# source_eagle.net
KiCad netlist of a schematic drawn in EAGLE
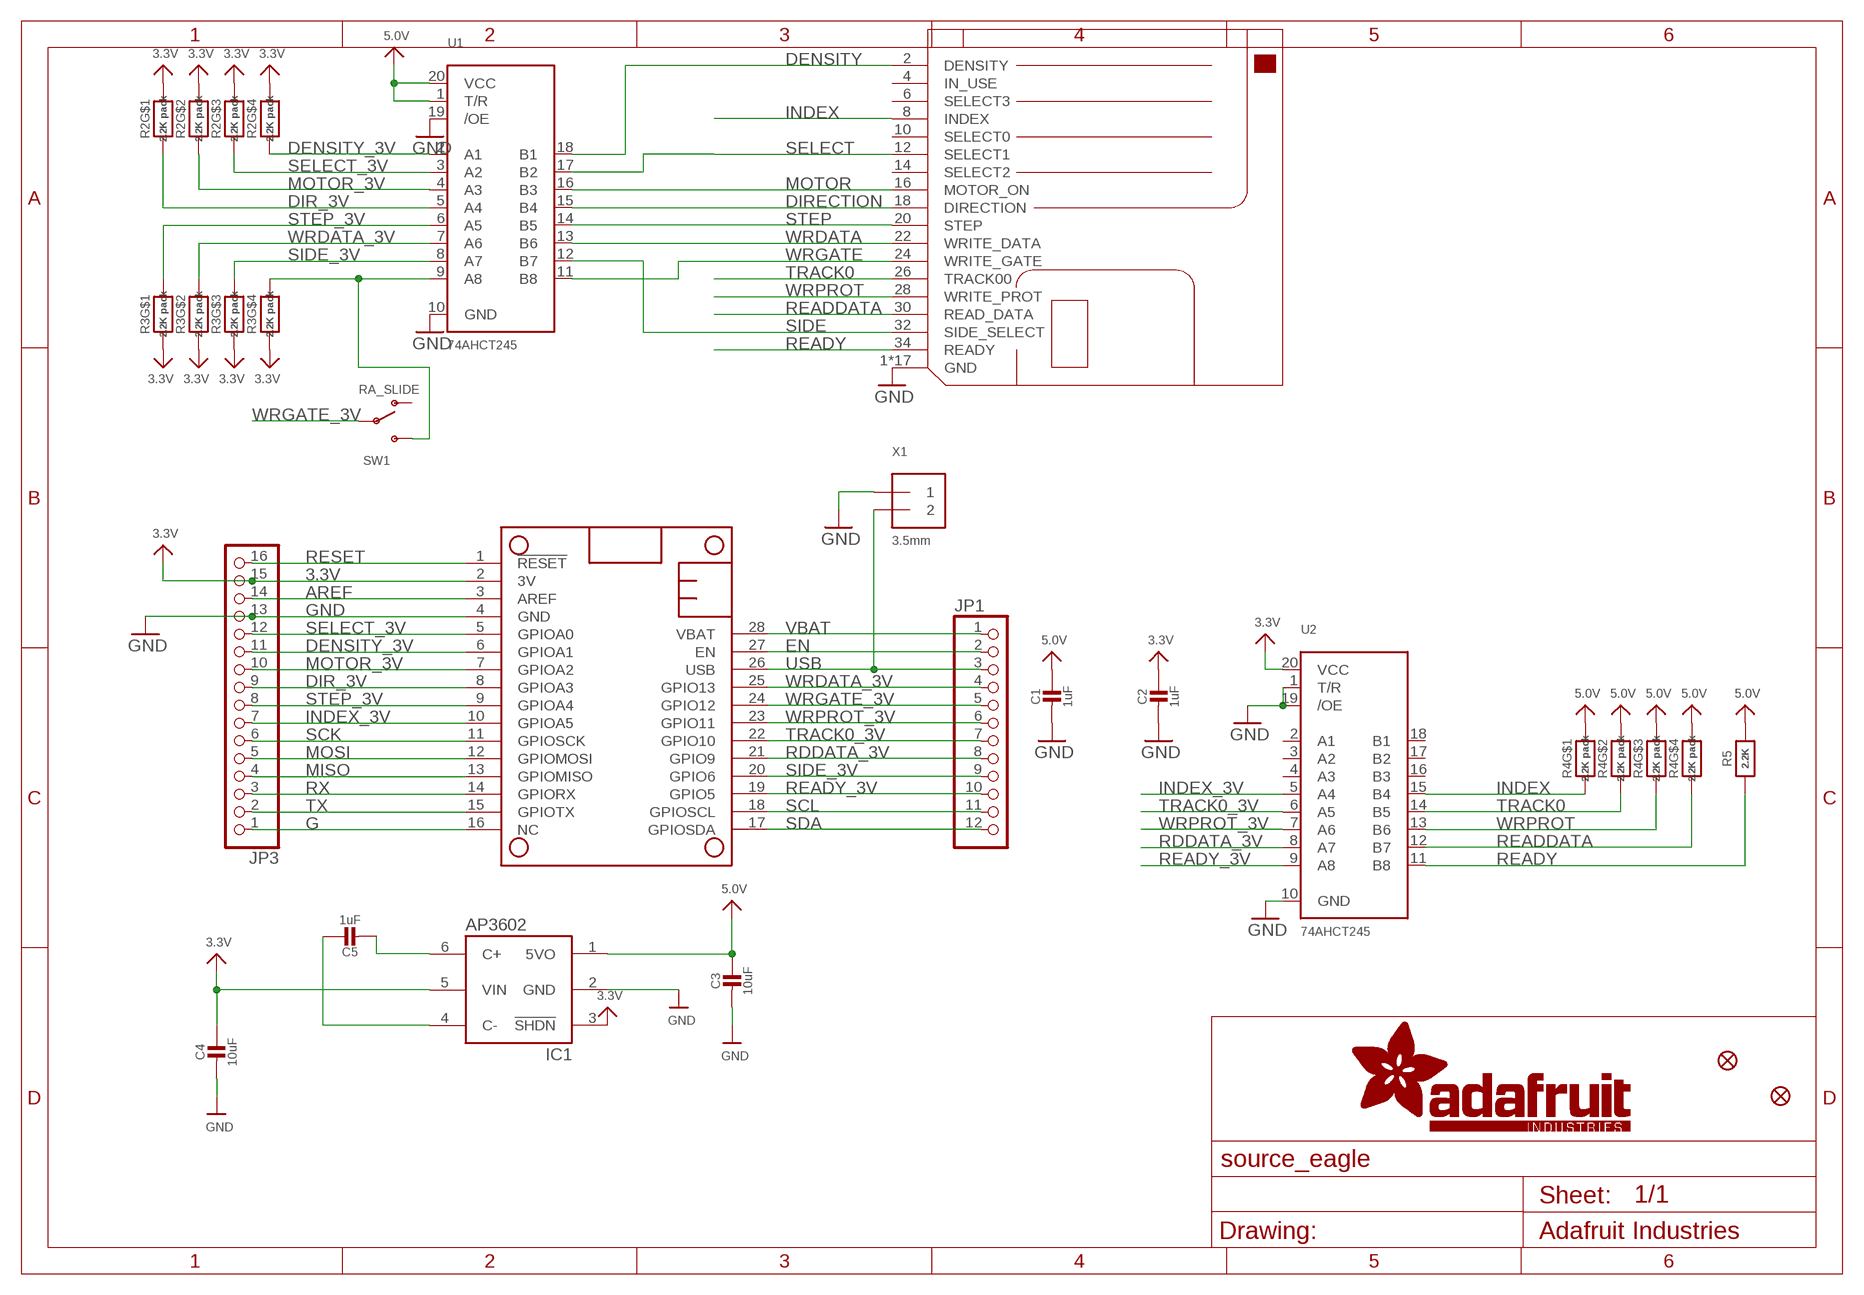
[diagram p0: schematic, sheet 1]

(export (version "E")
  (design (tool "Eeschema 10.0.6"))
  (components
    (comp (ref "C1")
      (value "1uF")
      (footprint "eagle-import:0603-NO")
      (libsource (lib "eagle-import") (part "CAP_CERAMIC0603_NO"))
    )
    (comp (ref "C2")
      (value "1uF")
      (footprint "eagle-import:0603-NO")
      (libsource (lib "eagle-import") (part "CAP_CERAMIC0603_NO"))
    )
    (comp (ref "C3")
      (value "10uF")
      (footprint "eagle-import:0805-NO")
      (libsource (lib "eagle-import") (part "CAP_CERAMIC0805-NOOUTLINE"))
    )
    (comp (ref "C4")
      (value "10uF")
      (footprint "eagle-import:0805-NO")
      (libsource (lib "eagle-import") (part "CAP_CERAMIC0805-NOOUTLINE"))
    )
    (comp (ref "C5")
      (value "1uF")
      (footprint "eagle-import:0603-NO")
      (libsource (lib "eagle-import") (part "CAP_CERAMIC0603_NO"))
    )
    (comp (ref "FDD1")
      (value "FLOPPY_IDC_SMT")
      (footprint "eagle-import:2X17_FLOPPY_SMTIDC")
      (libsource (lib "eagle-import") (part "FLOPPY_IDC_SMT"))
    )
    (comp (ref "FID1")
      (value "FIDUCIAL_1MM")
      (footprint "eagle-import:FIDUCIAL_1MM")
      (libsource (lib "eagle-import") (part "FIDUCIAL_1MM"))
    )
    (comp (ref "FID2")
      (value "FIDUCIAL_1MM")
      (footprint "eagle-import:FIDUCIAL_1MM")
      (libsource (lib "eagle-import") (part "FIDUCIAL_1MM"))
    )
    (comp (ref "IC1")
      (value "AP3602")
      (footprint "eagle-import:SOT23-6")
      (libsource (lib "eagle-import") (part "AP3602"))
    )
    (comp (ref "JP1")
      (value "HEADER-1X12")
      (footprint "eagle-import:1X12_ROUND")
      (libsource (lib "eagle-import") (part "HEADER-1X12"))
    )
    (comp (ref "JP3")
      (value "HEADER-1X16ROUND")
      (footprint "eagle-import:1X16_ROUND")
      (libsource (lib "eagle-import") (part "HEADER-1X16ROUND"))
    )
    (comp (ref "MS1")
      (value "FEATHERWING")
      (footprint "eagle-import:FEATHERWING")
      (libsource (lib "eagle-import") (part "FEATHERWING"))
    )
    (comp (ref "R2")
      (value "2.2K pack")
      (footprint "eagle-import:RESPACK_4X0603")
      (libsource (lib "eagle-import") (part "RESISTOR_4PACK"))
    )
    (comp (ref "R3")
      (value "2.2K pack")
      (footprint "eagle-import:RESPACK_4X0603")
      (libsource (lib "eagle-import") (part "RESISTOR_4PACK"))
    )
    (comp (ref "R4")
      (value "2.2K pack")
      (footprint "eagle-import:RESPACK_4X0603")
      (libsource (lib "eagle-import") (part "RESISTOR_4PACK"))
    )
    (comp (ref "R5")
      (value "2.2K")
      (footprint "eagle-import:0603-NO")
      (libsource (lib "eagle-import") (part "RESISTOR_0603_NOOUT"))
    )
    (comp (ref "SW1")
      (value "RA_SLIDE")
      (footprint "eagle-import:SPDT_SMT_SSSS811101")
      (libsource (lib "eagle-import") (part "SWITCH_SPDT"))
    )
    (comp (ref "U1")
      (value "74AHCT245")
      (footprint "eagle-import:SSOP20")
      (libsource (lib "eagle-import") (part "74LCX245_SSOP20"))
    )
    (comp (ref "U2")
      (value "74AHCT245")
      (footprint "eagle-import:SSOP20")
      (libsource (lib "eagle-import") (part "74LCX245_SSOP20"))
    )
    (comp (ref "X1")
      (value "3.5mm")
      (footprint "eagle-import:TERMBLOCK_1X2-3.5MM")
      (libsource (lib "eagle-import") (part "TERMBLOCK_1X2_3.5MM"))
    )
  )
  (nets
    (net (code "1") (name "/AREF") (class "Default")
      (node (ref "JP3") (pin "14") (pinfunction "14_14") (pintype "passive"))
      (node (ref "MS1") (pin "3") (pinfunction "AREF_3") (pintype "passive"))
    )
    (net (code "2") (name "/DENSITY") (class "Default")
      (node (ref "FDD1") (pin "2") (pinfunction "DENSITY_2") (pintype "input"))
      (node (ref "U1") (pin "18") (pinfunction "B1_18") (pintype "bidirectional"))
    )
    (net (code "3") (name "/DENSITY_3V") (class "Default")
      (node (ref "JP3") (pin "11") (pinfunction "11_11") (pintype "passive"))
      (node (ref "MS1") (pin "6") (pinfunction "GPIOA1_6") (pintype "bidirectional"))
      (node (ref "R2") (pin "4") (pinfunction "1_4") (pintype "passive"))
      (node (ref "U1") (pin "2") (pinfunction "A1_2") (pintype "bidirectional"))
    )
    (net (code "4") (name "/DIRECTION") (class "Default")
      (node (ref "FDD1") (pin "18") (pinfunction "DIRECTION_18") (pintype "input"))
      (node (ref "U1") (pin "15") (pinfunction "B4_15") (pintype "bidirectional"))
    )
    (net (code "5") (name "/DIR_3V") (class "Default")
      (node (ref "JP3") (pin "9") (pinfunction "9_9") (pintype "passive"))
      (node (ref "MS1") (pin "8") (pinfunction "GPIOA3_8") (pintype "bidirectional"))
      (node (ref "R2") (pin "1") (pinfunction "1_1") (pintype "passive"))
      (node (ref "U1") (pin "5") (pinfunction "A4_5") (pintype "bidirectional"))
    )
    (net (code "6") (name "/EN") (class "Default")
      (node (ref "JP1") (pin "2") (pinfunction "2_2") (pintype "passive"))
      (node (ref "MS1") (pin "27") (pinfunction "EN_27") (pintype "passive"))
    )
    (net (code "7") (name "/G") (class "Default")
      (node (ref "JP3") (pin "1") (pinfunction "1_1") (pintype "passive"))
      (node (ref "MS1") (pin "16") (pinfunction "NC_16") (pintype "passive"))
    )
    (net (code "8") (name "/INDEX") (class "Default")
      (node (ref "FDD1") (pin "8") (pinfunction "INDEX_8") (pintype "output"))
      (node (ref "R4") (pin "1") (pinfunction "1_1") (pintype "passive"))
      (node (ref "U2") (pin "15") (pinfunction "B4_15") (pintype "bidirectional"))
    )
    (net (code "9") (name "/INDEX_3V") (class "Default")
      (node (ref "JP3") (pin "7") (pinfunction "7_7") (pintype "passive"))
      (node (ref "MS1") (pin "10") (pinfunction "GPIOA5_10") (pintype "bidirectional"))
      (node (ref "U2") (pin "5") (pinfunction "A4_5") (pintype "bidirectional"))
    )
    (net (code "10") (name "/MISO") (class "Default")
      (node (ref "JP3") (pin "4") (pinfunction "4_4") (pintype "passive"))
      (node (ref "MS1") (pin "13") (pinfunction "GPIOMISO_13") (pintype "bidirectional"))
    )
    (net (code "11") (name "/MOSI") (class "Default")
      (node (ref "JP3") (pin "5") (pinfunction "5_5") (pintype "passive"))
      (node (ref "MS1") (pin "12") (pinfunction "GPIOMOSI_12") (pintype "bidirectional"))
    )
    (net (code "12") (name "/MOTOR") (class "Default")
      (node (ref "FDD1") (pin "16") (pinfunction "MOTOR_ON_16") (pintype "input"))
      (node (ref "U1") (pin "16") (pinfunction "B3_16") (pintype "bidirectional"))
    )
    (net (code "13") (name "/MOTOR_3V") (class "Default")
      (node (ref "JP3") (pin "10") (pinfunction "10_10") (pintype "passive"))
      (node (ref "MS1") (pin "7") (pinfunction "GPIOA2_7") (pintype "bidirectional"))
      (node (ref "R2") (pin "2") (pinfunction "1_2") (pintype "passive"))
      (node (ref "U1") (pin "4") (pinfunction "A3_4") (pintype "bidirectional"))
    )
    (net (code "14") (name "/RDDATA_3V") (class "Default")
      (node (ref "JP1") (pin "8") (pinfunction "8_8") (pintype "passive"))
      (node (ref "MS1") (pin "21") (pinfunction "GPIO9_21") (pintype "bidirectional"))
      (node (ref "U2") (pin "8") (pinfunction "A7_8") (pintype "bidirectional"))
    )
    (net (code "15") (name "/READDATA") (class "Default")
      (node (ref "FDD1") (pin "30") (pinfunction "READ_DATA_30") (pintype "output"))
      (node (ref "R4") (pin "4") (pinfunction "1_4") (pintype "passive"))
      (node (ref "U2") (pin "12") (pinfunction "B7_12") (pintype "bidirectional"))
    )
    (net (code "16") (name "/READY") (class "Default")
      (node (ref "FDD1") (pin "34") (pinfunction "READY_34") (pintype "output"))
      (node (ref "R5") (pin "1") (pinfunction "1_1") (pintype "passive"))
      (node (ref "U2") (pin "11") (pinfunction "B8_11") (pintype "bidirectional"))
    )
    (net (code "17") (name "/READY_3V") (class "Default")
      (node (ref "JP1") (pin "10") (pinfunction "10_10") (pintype "passive"))
      (node (ref "MS1") (pin "19") (pinfunction "GPIO5_19") (pintype "bidirectional"))
      (node (ref "U2") (pin "9") (pinfunction "A8_9") (pintype "bidirectional"))
    )
    (net (code "18") (name "/RESET") (class "Default")
      (node (ref "JP3") (pin "16") (pinfunction "16_16") (pintype "passive"))
      (node (ref "MS1") (pin "1") (pinfunction "~{RESET}_1") (pintype "input"))
    )
    (net (code "19") (name "/RX") (class "Default")
      (node (ref "JP3") (pin "3") (pinfunction "3_3") (pintype "passive"))
      (node (ref "MS1") (pin "14") (pinfunction "GPIORX_14") (pintype "bidirectional"))
    )
    (net (code "20") (name "/SCK") (class "Default")
      (node (ref "JP3") (pin "6") (pinfunction "6_6") (pintype "passive"))
      (node (ref "MS1") (pin "11") (pinfunction "GPIOSCK_11") (pintype "bidirectional"))
    )
    (net (code "21") (name "/SCL") (class "Default")
      (node (ref "JP1") (pin "11") (pinfunction "11_11") (pintype "passive"))
      (node (ref "MS1") (pin "18") (pinfunction "GPIOSCL_18") (pintype "bidirectional"))
    )
    (net (code "22") (name "/SDA") (class "Default")
      (node (ref "JP1") (pin "12") (pinfunction "12_12") (pintype "passive"))
      (node (ref "MS1") (pin "17") (pinfunction "GPIOSDA_17") (pintype "bidirectional"))
    )
    (net (code "23") (name "/SELECT") (class "Default")
      (node (ref "FDD1") (pin "12") (pinfunction "SELECT1_12") (pintype "input"))
      (node (ref "U1") (pin "17") (pinfunction "B2_17") (pintype "bidirectional"))
    )
    (net (code "24") (name "/SELECT_3V") (class "Default")
      (node (ref "JP3") (pin "12") (pinfunction "12_12") (pintype "passive"))
      (node (ref "MS1") (pin "5") (pinfunction "GPIOA0_5") (pintype "bidirectional"))
      (node (ref "R2") (pin "3") (pinfunction "1_3") (pintype "passive"))
      (node (ref "U1") (pin "3") (pinfunction "A2_3") (pintype "bidirectional"))
    )
    (net (code "25") (name "/SIDE") (class "Default")
      (node (ref "FDD1") (pin "32") (pinfunction "SIDE_SELECT_32") (pintype "input"))
      (node (ref "U1") (pin "12") (pinfunction "B7_12") (pintype "bidirectional"))
    )
    (net (code "26") (name "/SIDE_3V") (class "Default")
      (node (ref "JP1") (pin "9") (pinfunction "9_9") (pintype "passive"))
      (node (ref "MS1") (pin "20") (pinfunction "GPIO6_20") (pintype "bidirectional"))
      (node (ref "R3") (pin "6") (pinfunction "2_6") (pintype "passive"))
      (node (ref "U1") (pin "8") (pinfunction "A7_8") (pintype "bidirectional"))
    )
    (net (code "27") (name "/STEP") (class "Default")
      (node (ref "FDD1") (pin "20") (pinfunction "STEP_20") (pintype "input"))
      (node (ref "U1") (pin "14") (pinfunction "B5_14") (pintype "bidirectional"))
    )
    (net (code "28") (name "/STEP_3V") (class "Default")
      (node (ref "JP3") (pin "8") (pinfunction "8_8") (pintype "passive"))
      (node (ref "MS1") (pin "9") (pinfunction "GPIOA4_9") (pintype "bidirectional"))
      (node (ref "R3") (pin "8") (pinfunction "2_8") (pintype "passive"))
      (node (ref "U1") (pin "6") (pinfunction "A5_6") (pintype "bidirectional"))
    )
    (net (code "29") (name "/TRACK0") (class "Default")
      (node (ref "FDD1") (pin "26") (pinfunction "TRACK00_26") (pintype "output"))
      (node (ref "R4") (pin "2") (pinfunction "1_2") (pintype "passive"))
      (node (ref "U2") (pin "14") (pinfunction "B5_14") (pintype "bidirectional"))
    )
    (net (code "30") (name "/TRACK0_3V") (class "Default")
      (node (ref "JP1") (pin "7") (pinfunction "7_7") (pintype "passive"))
      (node (ref "MS1") (pin "22") (pinfunction "GPIO10_22") (pintype "bidirectional"))
      (node (ref "U2") (pin "6") (pinfunction "A5_6") (pintype "bidirectional"))
    )
    (net (code "31") (name "/TX") (class "Default")
      (node (ref "JP3") (pin "2") (pinfunction "2_2") (pintype "passive"))
      (node (ref "MS1") (pin "15") (pinfunction "GPIOTX_15") (pintype "bidirectional"))
    )
    (net (code "32") (name "/USB") (class "Default")
      (node (ref "JP1") (pin "3") (pinfunction "3_3") (pintype "passive"))
      (node (ref "MS1") (pin "26") (pinfunction "USB_26") (pintype "power_in"))
      (node (ref "X1") (pin "2") (pinfunction "2_2") (pintype "passive"))
    )
    (net (code "33") (name "/VBAT") (class "Default")
      (node (ref "JP1") (pin "1") (pinfunction "1_1") (pintype "passive"))
      (node (ref "MS1") (pin "28") (pinfunction "VBAT_28") (pintype "power_in"))
    )
    (net (code "34") (name "/WRDATA") (class "Default")
      (node (ref "FDD1") (pin "22") (pinfunction "WRITE_DATA_22") (pintype "input"))
      (node (ref "U1") (pin "13") (pinfunction "B6_13") (pintype "bidirectional"))
    )
    (net (code "35") (name "/WRDATA_3V") (class "Default")
      (node (ref "JP1") (pin "4") (pinfunction "4_4") (pintype "passive"))
      (node (ref "MS1") (pin "25") (pinfunction "GPIO13_25") (pintype "bidirectional"))
      (node (ref "R3") (pin "7") (pinfunction "2_7") (pintype "passive"))
      (node (ref "U1") (pin "7") (pinfunction "A6_7") (pintype "bidirectional"))
    )
    (net (code "36") (name "/WRGATE") (class "Default")
      (node (ref "FDD1") (pin "24") (pinfunction "WRITE_GATE_24") (pintype "input"))
      (node (ref "U1") (pin "11") (pinfunction "B8_11") (pintype "bidirectional"))
    )
    (net (code "37") (name "/WRGATE_3V") (class "Default")
      (node (ref "JP1") (pin "5") (pinfunction "5_5") (pintype "passive"))
      (node (ref "MS1") (pin "24") (pinfunction "GPIO12_24") (pintype "bidirectional"))
      (node (ref "SW1") (pin "B") (pinfunction "P_B") (pintype "passive"))
    )
    (net (code "38") (name "/WRPROT") (class "Default")
      (node (ref "FDD1") (pin "28") (pinfunction "WRITE_PROT_28") (pintype "output"))
      (node (ref "R4") (pin "3") (pinfunction "1_3") (pintype "passive"))
      (node (ref "U2") (pin "13") (pinfunction "B6_13") (pintype "bidirectional"))
    )
    (net (code "39") (name "/WRPROT_3V") (class "Default")
      (node (ref "JP1") (pin "6") (pinfunction "6_6") (pintype "passive"))
      (node (ref "MS1") (pin "23") (pinfunction "GPIO11_23") (pintype "bidirectional"))
      (node (ref "U2") (pin "7") (pinfunction "A6_7") (pintype "bidirectional"))
    )
    (net (code "40") (name "3.3V") (class "Default")
      (node (ref "C2") (pin "1") (pinfunction "1_1") (pintype "passive"))
      (node (ref "C4") (pin "1") (pinfunction "1_1") (pintype "passive"))
      (node (ref "IC1") (pin "3") (pinfunction "~{SHDN}_3") (pintype "input"))
      (node (ref "IC1") (pin "5") (pinfunction "VIN_5") (pintype "power_in"))
      (node (ref "JP3") (pin "15") (pinfunction "15_15") (pintype "passive"))
      (node (ref "MS1") (pin "2") (pinfunction "3V_2") (pintype "power_in"))
      (node (ref "R2") (pin "5") (pinfunction "2_5") (pintype "passive"))
      (node (ref "R2") (pin "6") (pinfunction "2_6") (pintype "passive"))
      (node (ref "R2") (pin "7") (pinfunction "2_7") (pintype "passive"))
      (node (ref "R2") (pin "8") (pinfunction "2_8") (pintype "passive"))
      (node (ref "R3") (pin "1") (pinfunction "1_1") (pintype "passive"))
      (node (ref "R3") (pin "2") (pinfunction "1_2") (pintype "passive"))
      (node (ref "R3") (pin "3") (pinfunction "1_3") (pintype "passive"))
      (node (ref "R3") (pin "4") (pinfunction "1_4") (pintype "passive"))
      (node (ref "U2") (pin "20") (pinfunction "VCC_20") (pintype "bidirectional"))
    )
    (net (code "41") (name "5.0V") (class "Default")
      (node (ref "C1") (pin "1") (pinfunction "1_1") (pintype "passive"))
      (node (ref "C3") (pin "1") (pinfunction "1_1") (pintype "passive"))
      (node (ref "IC1") (pin "1") (pinfunction "5VO_1") (pintype "power_in"))
      (node (ref "R4") (pin "5") (pinfunction "2_5") (pintype "passive"))
      (node (ref "R4") (pin "6") (pinfunction "2_6") (pintype "passive"))
      (node (ref "R4") (pin "7") (pinfunction "2_7") (pintype "passive"))
      (node (ref "R4") (pin "8") (pinfunction "2_8") (pintype "passive"))
      (node (ref "R5") (pin "2") (pinfunction "2_2") (pintype "passive"))
      (node (ref "U1") (pin "1") (pinfunction "T/R_1") (pintype "bidirectional"))
      (node (ref "U1") (pin "20") (pinfunction "VCC_20") (pintype "bidirectional"))
    )
    (net (code "42") (name "GND") (class "Default")
      (node (ref "C1") (pin "2") (pinfunction "2_2") (pintype "passive"))
      (node (ref "C2") (pin "2") (pinfunction "2_2") (pintype "passive"))
      (node (ref "C3") (pin "2") (pinfunction "2_2") (pintype "passive"))
      (node (ref "C4") (pin "2") (pinfunction "2_2") (pintype "passive"))
      (node (ref "FDD1") (pin "1") (pinfunction "GND_1") (pintype "power_in"))
      (node (ref "FDD1") (pin "11") (pinfunction "GND_11") (pintype "power_in"))
      (node (ref "FDD1") (pin "13") (pinfunction "GND_13") (pintype "power_in"))
      (node (ref "FDD1") (pin "15") (pinfunction "GND_15") (pintype "power_in"))
      (node (ref "FDD1") (pin "17") (pinfunction "GND_17") (pintype "power_in"))
      (node (ref "FDD1") (pin "19") (pinfunction "GND_19") (pintype "power_in"))
      (node (ref "FDD1") (pin "21") (pinfunction "GND_21") (pintype "power_in"))
      (node (ref "FDD1") (pin "23") (pinfunction "GND_23") (pintype "power_in"))
      (node (ref "FDD1") (pin "25") (pinfunction "GND_25") (pintype "power_in"))
      (node (ref "FDD1") (pin "27") (pinfunction "GND_27") (pintype "power_in"))
      (node (ref "FDD1") (pin "29") (pinfunction "GND_29") (pintype "power_in"))
      (node (ref "FDD1") (pin "3") (pinfunction "GND_3") (pintype "power_in"))
      (node (ref "FDD1") (pin "31") (pinfunction "GND_31") (pintype "power_in"))
      (node (ref "FDD1") (pin "33") (pinfunction "GND_33") (pintype "power_in"))
      (node (ref "FDD1") (pin "5") (pinfunction "GND_5") (pintype "power_in"))
      (node (ref "FDD1") (pin "7") (pinfunction "GND_7") (pintype "power_in"))
      (node (ref "FDD1") (pin "9") (pinfunction "GND_9") (pintype "power_in"))
      (node (ref "IC1") (pin "2") (pinfunction "GND_2") (pintype "power_in"))
      (node (ref "JP3") (pin "13") (pinfunction "13_13") (pintype "passive"))
      (node (ref "MS1") (pin "4") (pinfunction "GND_4") (pintype "power_in"))
      (node (ref "U1") (pin "10") (pinfunction "GND_10") (pintype "bidirectional"))
      (node (ref "U1") (pin "19") (pinfunction "/OE_19") (pintype "bidirectional"))
      (node (ref "U2") (pin "1") (pinfunction "T/R_1") (pintype "bidirectional"))
      (node (ref "U2") (pin "10") (pinfunction "GND_10") (pintype "bidirectional"))
      (node (ref "U2") (pin "19") (pinfunction "/OE_19") (pintype "bidirectional"))
      (node (ref "X1") (pin "1") (pinfunction "1_1") (pintype "passive"))
    )
    (net (code "43") (name "Net-(IC1-C+)") (class "Default")
      (node (ref "C5") (pin "2") (pinfunction "2_2") (pintype "passive"))
      (node (ref "IC1") (pin "6") (pinfunction "C+_6") (pintype "bidirectional"))
    )
    (net (code "44") (name "Net-(IC1-C-)") (class "Default")
      (node (ref "C5") (pin "1") (pinfunction "1_1") (pintype "passive"))
      (node (ref "IC1") (pin "4") (pinfunction "C-_4") (pintype "bidirectional"))
    )
    (net (code "45") (name "Net-(R3D-2)") (class "Default")
      (node (ref "R3") (pin "5") (pinfunction "2_5") (pintype "passive"))
      (node (ref "SW1") (pin "C") (pinfunction "S_C") (pintype "passive"))
      (node (ref "U1") (pin "9") (pinfunction "A8_9") (pintype "bidirectional"))
    )
    (net (code "46") (name "unconnected-(FDD1-IN_USE-Pad4)") (class "Default")
      (node (ref "FDD1") (pin "4") (pinfunction "IN_USE_4") (pintype "input"))
    )
    (net (code "47") (name "unconnected-(FDD1-SELECT0-Pad10)") (class "Default")
      (node (ref "FDD1") (pin "10") (pinfunction "SELECT0_10") (pintype "input"))
    )
    (net (code "48") (name "unconnected-(FDD1-SELECT2-Pad14)") (class "Default")
      (node (ref "FDD1") (pin "14") (pinfunction "SELECT2_14") (pintype "input"))
    )
    (net (code "49") (name "unconnected-(FDD1-SELECT3-Pad6)") (class "Default")
      (node (ref "FDD1") (pin "6") (pinfunction "SELECT3_6") (pintype "input"))
    )
    (net (code "50") (name "unconnected-(SW1-O-PadA)") (class "Default")
      (node (ref "SW1") (pin "A") (pinfunction "O_A") (pintype "passive"))
    )
    (net (code "51") (name "unconnected-(U2-A1-Pad2)") (class "Default")
      (node (ref "U2") (pin "2") (pinfunction "A1_2") (pintype "bidirectional"))
    )
    (net (code "52") (name "unconnected-(U2-A2-Pad3)") (class "Default")
      (node (ref "U2") (pin "3") (pinfunction "A2_3") (pintype "bidirectional"))
    )
    (net (code "53") (name "unconnected-(U2-A3-Pad4)") (class "Default")
      (node (ref "U2") (pin "4") (pinfunction "A3_4") (pintype "bidirectional"))
    )
    (net (code "54") (name "unconnected-(U2-B1-Pad18)") (class "Default")
      (node (ref "U2") (pin "18") (pinfunction "B1_18") (pintype "bidirectional"))
    )
    (net (code "55") (name "unconnected-(U2-B2-Pad17)") (class "Default")
      (node (ref "U2") (pin "17") (pinfunction "B2_17") (pintype "bidirectional"))
    )
    (net (code "56") (name "unconnected-(U2-B3-Pad16)") (class "Default")
      (node (ref "U2") (pin "16") (pinfunction "B3_16") (pintype "bidirectional"))
    )
  )
)
